# Zavrsni.net
KiCad netlist of a schematic drawn in Altium Designer
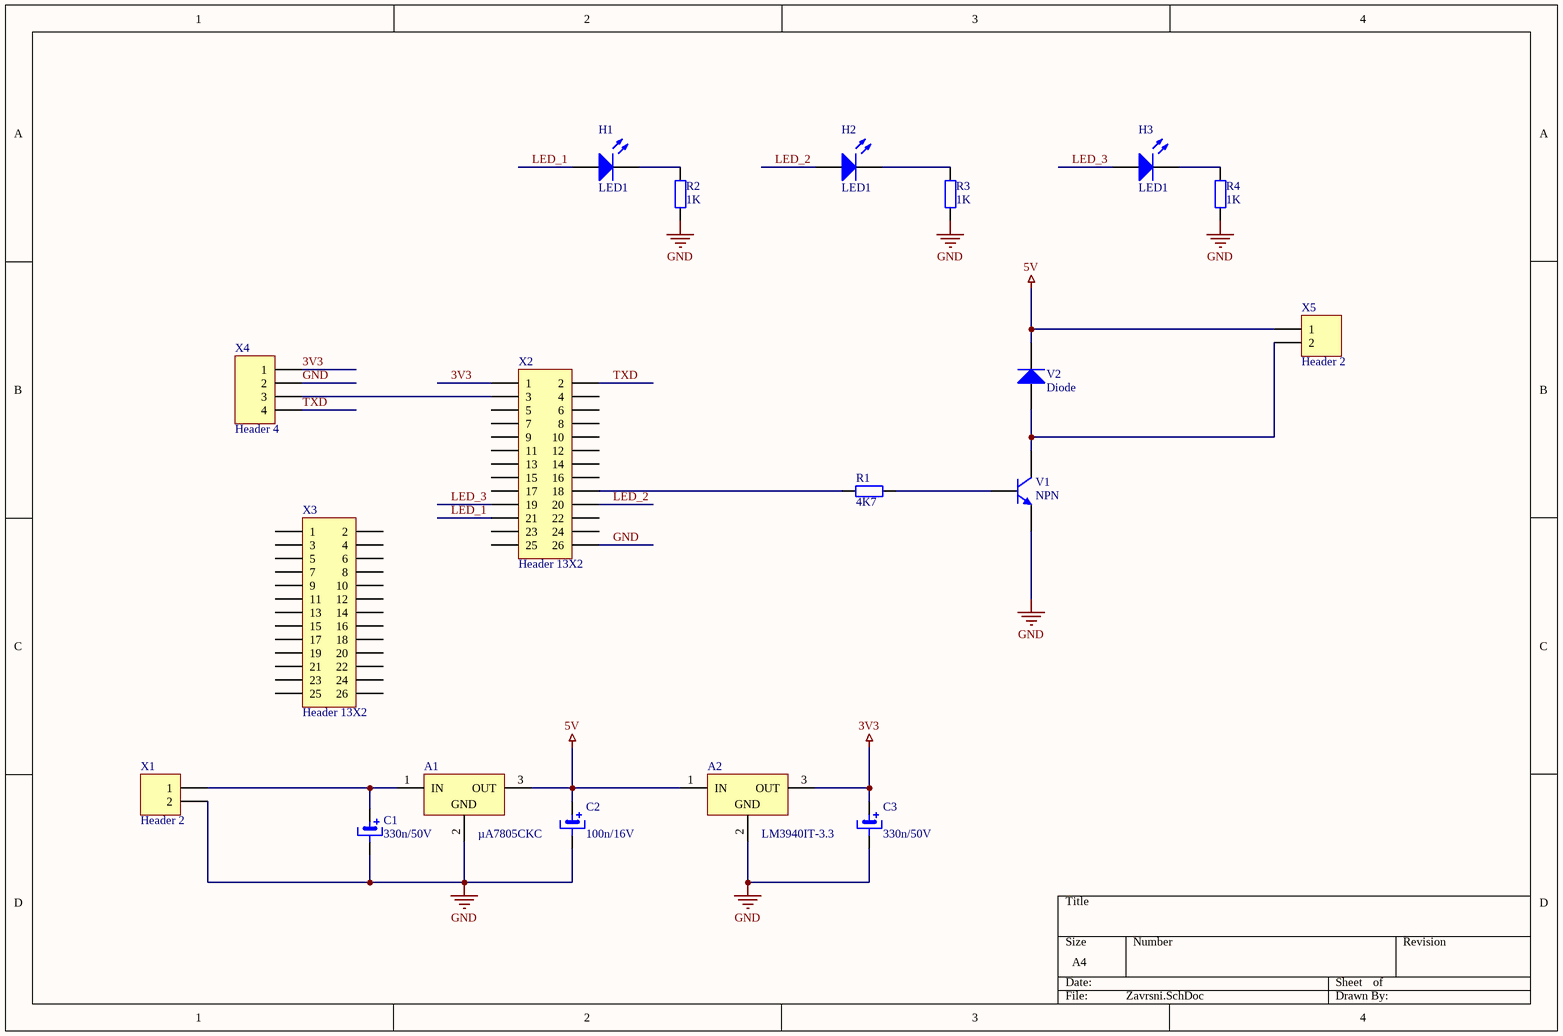
[diagram p0: Zavrsni.SchDoc]

(export (version "E")
  (design (tool "Eeschema 10.0.6"))
  (components
    (comp (ref "A1")
      (value "µA7805CKC")
      (footprint "KC03")
      (description "Positive-Voltage Regulator")
      (fields (field (name "PUBLISHER") "Altium Limited"))
      (libsource (lib "TI Power Mgt Voltage Regulator") (part "µA7805CKC"))
    )
    (comp (ref "A2")
      (value "LM3940IT-3.3")
      (footprint "T03B")
      (description "1A Low Dropout Regulator for 5V to 3.3V Conversion, 3-pin TO-220")
      (fields
        (field (name "MANUFACTURER") "National Semiconductor")
        (field (name "PUBLISHER") "Altium Limited")
      )
      (libsource (lib "NSC LDO") (part "LM3940IT-3.3"))
    )
    (comp (ref "C1")
      (value "330n/50V")
      (footprint "CAPPR2-5x6.8")
      (description "Electrolytic capacitor")
      (libsource (lib "Zavrsni") (part "Elko"))
    )
    (comp (ref "C2")
      (value "100n/16V")
      (footprint "CAPPR2-5x6.8")
      (description "Electrolytic capacitor")
      (libsource (lib "Zavrsni") (part "Elko"))
    )
    (comp (ref "C3")
      (value "330n/50V")
      (footprint "CAPPR2-5x6.8")
      (description "Electrolytic capacitor")
      (libsource (lib "Zavrsni") (part "Elko"))
    )
    (comp (ref "H1")
      (value "LED1")
      (footprint "LED dioda")
      (description "Typical RED GaAs LED")
      (fields (field (name "PUBLISHER") "Altium Limited"))
      (libsource (lib "Miscellaneous Devices") (part "LED1"))
    )
    (comp (ref "H2")
      (value "LED1")
      (footprint "LED dioda")
      (description "Typical RED GaAs LED")
      (fields (field (name "PUBLISHER") "Altium Limited"))
      (libsource (lib "Miscellaneous Devices") (part "LED1"))
    )
    (comp (ref "H3")
      (value "LED1")
      (footprint "LED dioda")
      (description "Typical RED GaAs LED")
      (fields (field (name "PUBLISHER") "Altium Limited"))
      (libsource (lib "Miscellaneous Devices") (part "LED1"))
    )
    (comp (ref "R1")
      (value "4K7")
      (footprint "AXIAL-0.4")
      (description "Resistor")
      (fields (field (name "PUBLISHER") "Altium Limited"))
      (libsource (lib "") (part "Res2_1"))
    )
    (comp (ref "R2")
      (value "1K")
      (footprint "2012[0805]")
      (description "Resistor")
      (fields (field (name "PUBLISHER") "Altium Limited"))
      (libsource (lib "Miscellaneous Devices") (part "Res2"))
    )
    (comp (ref "R3")
      (value "1K")
      (footprint "2012[0805]")
      (description "Resistor")
      (fields (field (name "PUBLISHER") "Altium Limited"))
      (libsource (lib "Miscellaneous Devices") (part "Res2"))
    )
    (comp (ref "R4")
      (value "1K")
      (footprint "2012[0805]")
      (description "Resistor")
      (fields (field (name "PUBLISHER") "Altium Limited"))
      (libsource (lib "Miscellaneous Devices") (part "Res2"))
    )
    (comp (ref "V1")
      (value "NPN")
      (footprint "TO-226-AA")
      (description "NPN Bipolar Transistor")
      (fields (field (name "PUBLISHER") "Altium Limited"))
      (libsource (lib "Miscellaneous Devices") (part "NPN"))
    )
    (comp (ref "V2")
      (value "Diode")
      (footprint "DIODE-0.4")
      (description "Default Diode")
      (fields (field (name "PUBLISHER") "Altium Limited"))
      (libsource (lib "Miscellaneous Devices") (part "Diode"))
    )
    (comp (ref "X1")
      (value "Header 2")
      (footprint "HDR1X2")
      (description "Header, 2-Pin")
      (fields (field (name "PUBLISHER") "Altium Limited"))
      (libsource (lib "") (part "Header 2_1"))
    )
    (comp (ref "X2")
      (value "Header 13X2")
      (footprint "HDR2X13")
      (description "Header, 13-Pin, Dual row")
      (fields (field (name "PUBLISHER") "Altium Limited"))
      (libsource (lib "Miscellaneous Connectors") (part "Header 13X2"))
    )
    (comp (ref "X3")
      (value "Header 13X2")
      (footprint "HDR2X13")
      (description "Header, 13-Pin, Dual row")
      (fields (field (name "PUBLISHER") "Altium Limited"))
      (libsource (lib "Miscellaneous Connectors") (part "Header 13X2"))
    )
    (comp (ref "X4")
      (value "Header 4")
      (footprint "HDR1X4")
      (description "Header, 4-Pin")
      (fields (field (name "PUBLISHER") "Altium Limited"))
      (libsource (lib "Miscellaneous Connectors") (part "Header 4"))
    )
    (comp (ref "X5")
      (value "Header 2")
      (footprint "HDR1X2")
      (description "Header, 2-Pin")
      (fields (field (name "PUBLISHER") "Altium Limited"))
      (libsource (lib "Miscellaneous Connectors") (part "Header 2"))
    )
  )
  (nets
    (net (code "1") (name "/LED_1") (class "Default")
      (node (ref "H1") (pin "1") (pinfunction "A_1") (pintype "passive"))
      (node (ref "X2") (pin "21") (pinfunction "21_21") (pintype "passive"))
    )
    (net (code "2") (name "/LED_2") (class "Default")
      (node (ref "H2") (pin "1") (pinfunction "A_1") (pintype "passive"))
      (node (ref "X2") (pin "20") (pinfunction "20_20") (pintype "passive"))
    )
    (net (code "3") (name "/LED_3") (class "Default")
      (node (ref "H3") (pin "1") (pinfunction "A_1") (pintype "passive"))
      (node (ref "X2") (pin "19") (pinfunction "19_19") (pintype "passive"))
    )
    (net (code "4") (name "/TXD") (class "Default")
      (node (ref "X2") (pin "2") (pinfunction "2_2") (pintype "passive"))
      (node (ref "X4") (pin "4") (pinfunction "4_4") (pintype "passive"))
    )
    (net (code "5") (name "3V3") (class "Default")
      (node (ref "A2") (pin "3") (pinfunction "OUT_3") (pintype "power_in"))
      (node (ref "C3") (pin "1") (pinfunction "1_1") (pintype "passive"))
      (node (ref "X2") (pin "1") (pinfunction "1_1") (pintype "passive"))
      (node (ref "X4") (pin "1") (pinfunction "1_1") (pintype "passive"))
    )
    (net (code "6") (name "5V") (class "Default")
      (node (ref "A1") (pin "3") (pinfunction "OUT_3") (pintype "power_in"))
      (node (ref "A2") (pin "1") (pinfunction "IN_1") (pintype "power_in"))
      (node (ref "C2") (pin "1") (pinfunction "1_1") (pintype "passive"))
      (node (ref "V2") (pin "2") (pinfunction "K_2") (pintype "passive"))
      (node (ref "X5") (pin "1") (pinfunction "1_1") (pintype "passive"))
    )
    (net (code "7") (name "GND") (class "Default")
      (node (ref "A1") (pin "2") (pinfunction "GND_2") (pintype "power_in"))
      (node (ref "A2") (pin "2") (pinfunction "GND_2") (pintype "power_in"))
      (node (ref "C1") (pin "2") (pinfunction "2_2") (pintype "passive"))
      (node (ref "C2") (pin "2") (pinfunction "2_2") (pintype "passive"))
      (node (ref "C3") (pin "2") (pinfunction "2_2") (pintype "passive"))
      (node (ref "R2") (pin "1") (pinfunction "1_1") (pintype "passive"))
      (node (ref "R3") (pin "1") (pinfunction "1_1") (pintype "passive"))
      (node (ref "R4") (pin "1") (pinfunction "1_1") (pintype "passive"))
      (node (ref "V1") (pin "3") (pinfunction "E_3") (pintype "passive"))
      (node (ref "X1") (pin "2") (pinfunction "2_2") (pintype "passive"))
      (node (ref "X2") (pin "26") (pinfunction "26_26") (pintype "passive"))
      (node (ref "X4") (pin "2") (pinfunction "2_2") (pintype "passive"))
    )
    (net (code "8") (name "Net-(A1-IN)") (class "Default")
      (node (ref "A1") (pin "1") (pinfunction "IN_1") (pintype "power_in"))
      (node (ref "C1") (pin "1") (pinfunction "1_1") (pintype "passive"))
      (node (ref "X1") (pin "1") (pinfunction "1_1") (pintype "passive"))
    )
    (net (code "9") (name "Net-(H1-K)") (class "Default")
      (node (ref "H1") (pin "2") (pinfunction "K_2") (pintype "passive"))
      (node (ref "R2") (pin "2") (pinfunction "2_2") (pintype "passive"))
    )
    (net (code "10") (name "Net-(H2-K)") (class "Default")
      (node (ref "H2") (pin "2") (pinfunction "K_2") (pintype "passive"))
      (node (ref "R3") (pin "2") (pinfunction "2_2") (pintype "passive"))
    )
    (net (code "11") (name "Net-(H3-K)") (class "Default")
      (node (ref "H3") (pin "2") (pinfunction "K_2") (pintype "passive"))
      (node (ref "R4") (pin "2") (pinfunction "2_2") (pintype "passive"))
    )
    (net (code "12") (name "Net-(R1-Pad1)") (class "Default")
      (node (ref "R1") (pin "1") (pinfunction "1_1") (pintype "passive"))
      (node (ref "X2") (pin "18") (pinfunction "18_18") (pintype "passive"))
    )
    (net (code "13") (name "Net-(V1-B)") (class "Default")
      (node (ref "R1") (pin "2") (pinfunction "2_2") (pintype "passive"))
      (node (ref "V1") (pin "2") (pinfunction "B_2") (pintype "passive"))
    )
    (net (code "14") (name "Net-(V1-C)") (class "Default")
      (node (ref "V1") (pin "1") (pinfunction "C_1") (pintype "passive"))
      (node (ref "V2") (pin "1") (pinfunction "A_1") (pintype "passive"))
      (node (ref "X5") (pin "2") (pinfunction "2_2") (pintype "passive"))
    )
    (net (code "15") (name "Net-(X2-Pad3)") (class "Default")
      (node (ref "X2") (pin "3") (pinfunction "3_3") (pintype "passive"))
      (node (ref "X4") (pin "3") (pinfunction "3_3") (pintype "passive"))
    )
    (net (code "16") (name "unconnected-(X2-Pad4)") (class "Default")
      (node (ref "X2") (pin "4") (pinfunction "4_4") (pintype "passive"))
    )
    (net (code "17") (name "unconnected-(X2-Pad5)") (class "Default")
      (node (ref "X2") (pin "5") (pinfunction "5_5") (pintype "passive"))
    )
    (net (code "18") (name "unconnected-(X2-Pad6)") (class "Default")
      (node (ref "X2") (pin "6") (pinfunction "6_6") (pintype "passive"))
    )
    (net (code "19") (name "unconnected-(X2-Pad7)") (class "Default")
      (node (ref "X2") (pin "7") (pinfunction "7_7") (pintype "passive"))
    )
    (net (code "20") (name "unconnected-(X2-Pad8)") (class "Default")
      (node (ref "X2") (pin "8") (pinfunction "8_8") (pintype "passive"))
    )
    (net (code "21") (name "unconnected-(X2-Pad9)") (class "Default")
      (node (ref "X2") (pin "9") (pinfunction "9_9") (pintype "passive"))
    )
    (net (code "22") (name "unconnected-(X2-Pad10)") (class "Default")
      (node (ref "X2") (pin "10") (pinfunction "10_10") (pintype "passive"))
    )
    (net (code "23") (name "unconnected-(X2-Pad11)") (class "Default")
      (node (ref "X2") (pin "11") (pinfunction "11_11") (pintype "passive"))
    )
    (net (code "24") (name "unconnected-(X2-Pad12)") (class "Default")
      (node (ref "X2") (pin "12") (pinfunction "12_12") (pintype "passive"))
    )
    (net (code "25") (name "unconnected-(X2-Pad13)") (class "Default")
      (node (ref "X2") (pin "13") (pinfunction "13_13") (pintype "passive"))
    )
    (net (code "26") (name "unconnected-(X2-Pad14)") (class "Default")
      (node (ref "X2") (pin "14") (pinfunction "14_14") (pintype "passive"))
    )
    (net (code "27") (name "unconnected-(X2-Pad15)") (class "Default")
      (node (ref "X2") (pin "15") (pinfunction "15_15") (pintype "passive"))
    )
    (net (code "28") (name "unconnected-(X2-Pad16)") (class "Default")
      (node (ref "X2") (pin "16") (pinfunction "16_16") (pintype "passive"))
    )
    (net (code "29") (name "unconnected-(X2-Pad17)") (class "Default")
      (node (ref "X2") (pin "17") (pinfunction "17_17") (pintype "passive"))
    )
    (net (code "30") (name "unconnected-(X2-Pad22)") (class "Default")
      (node (ref "X2") (pin "22") (pinfunction "22_22") (pintype "passive"))
    )
    (net (code "31") (name "unconnected-(X2-Pad23)") (class "Default")
      (node (ref "X2") (pin "23") (pinfunction "23_23") (pintype "passive"))
    )
    (net (code "32") (name "unconnected-(X2-Pad24)") (class "Default")
      (node (ref "X2") (pin "24") (pinfunction "24_24") (pintype "passive"))
    )
    (net (code "33") (name "unconnected-(X2-Pad25)") (class "Default")
      (node (ref "X2") (pin "25") (pinfunction "25_25") (pintype "passive"))
    )
    (net (code "34") (name "unconnected-(X3-Pad1)") (class "Default")
      (node (ref "X3") (pin "1") (pinfunction "1_1") (pintype "passive"))
    )
    (net (code "35") (name "unconnected-(X3-Pad2)") (class "Default")
      (node (ref "X3") (pin "2") (pinfunction "2_2") (pintype "passive"))
    )
    (net (code "36") (name "unconnected-(X3-Pad3)") (class "Default")
      (node (ref "X3") (pin "3") (pinfunction "3_3") (pintype "passive"))
    )
    (net (code "37") (name "unconnected-(X3-Pad4)") (class "Default")
      (node (ref "X3") (pin "4") (pinfunction "4_4") (pintype "passive"))
    )
    (net (code "38") (name "unconnected-(X3-Pad5)") (class "Default")
      (node (ref "X3") (pin "5") (pinfunction "5_5") (pintype "passive"))
    )
    (net (code "39") (name "unconnected-(X3-Pad6)") (class "Default")
      (node (ref "X3") (pin "6") (pinfunction "6_6") (pintype "passive"))
    )
    (net (code "40") (name "unconnected-(X3-Pad7)") (class "Default")
      (node (ref "X3") (pin "7") (pinfunction "7_7") (pintype "passive"))
    )
    (net (code "41") (name "unconnected-(X3-Pad8)") (class "Default")
      (node (ref "X3") (pin "8") (pinfunction "8_8") (pintype "passive"))
    )
    (net (code "42") (name "unconnected-(X3-Pad9)") (class "Default")
      (node (ref "X3") (pin "9") (pinfunction "9_9") (pintype "passive"))
    )
    (net (code "43") (name "unconnected-(X3-Pad10)") (class "Default")
      (node (ref "X3") (pin "10") (pinfunction "10_10") (pintype "passive"))
    )
    (net (code "44") (name "unconnected-(X3-Pad11)") (class "Default")
      (node (ref "X3") (pin "11") (pinfunction "11_11") (pintype "passive"))
    )
    (net (code "45") (name "unconnected-(X3-Pad12)") (class "Default")
      (node (ref "X3") (pin "12") (pinfunction "12_12") (pintype "passive"))
    )
    (net (code "46") (name "unconnected-(X3-Pad13)") (class "Default")
      (node (ref "X3") (pin "13") (pinfunction "13_13") (pintype "passive"))
    )
    (net (code "47") (name "unconnected-(X3-Pad14)") (class "Default")
      (node (ref "X3") (pin "14") (pinfunction "14_14") (pintype "passive"))
    )
    (net (code "48") (name "unconnected-(X3-Pad15)") (class "Default")
      (node (ref "X3") (pin "15") (pinfunction "15_15") (pintype "passive"))
    )
    (net (code "49") (name "unconnected-(X3-Pad16)") (class "Default")
      (node (ref "X3") (pin "16") (pinfunction "16_16") (pintype "passive"))
    )
    (net (code "50") (name "unconnected-(X3-Pad17)") (class "Default")
      (node (ref "X3") (pin "17") (pinfunction "17_17") (pintype "passive"))
    )
    (net (code "51") (name "unconnected-(X3-Pad18)") (class "Default")
      (node (ref "X3") (pin "18") (pinfunction "18_18") (pintype "passive"))
    )
    (net (code "52") (name "unconnected-(X3-Pad19)") (class "Default")
      (node (ref "X3") (pin "19") (pinfunction "19_19") (pintype "passive"))
    )
    (net (code "53") (name "unconnected-(X3-Pad20)") (class "Default")
      (node (ref "X3") (pin "20") (pinfunction "20_20") (pintype "passive"))
    )
    (net (code "54") (name "unconnected-(X3-Pad21)") (class "Default")
      (node (ref "X3") (pin "21") (pinfunction "21_21") (pintype "passive"))
    )
    (net (code "55") (name "unconnected-(X3-Pad22)") (class "Default")
      (node (ref "X3") (pin "22") (pinfunction "22_22") (pintype "passive"))
    )
    (net (code "56") (name "unconnected-(X3-Pad23)") (class "Default")
      (node (ref "X3") (pin "23") (pinfunction "23_23") (pintype "passive"))
    )
    (net (code "57") (name "unconnected-(X3-Pad24)") (class "Default")
      (node (ref "X3") (pin "24") (pinfunction "24_24") (pintype "passive"))
    )
    (net (code "58") (name "unconnected-(X3-Pad25)") (class "Default")
      (node (ref "X3") (pin "25") (pinfunction "25_25") (pintype "passive"))
    )
    (net (code "59") (name "unconnected-(X3-Pad26)") (class "Default")
      (node (ref "X3") (pin "26") (pinfunction "26_26") (pintype "passive"))
    )
  )
)
